# ADC.net
KiCad netlist of a schematic drawn in Altium Designer
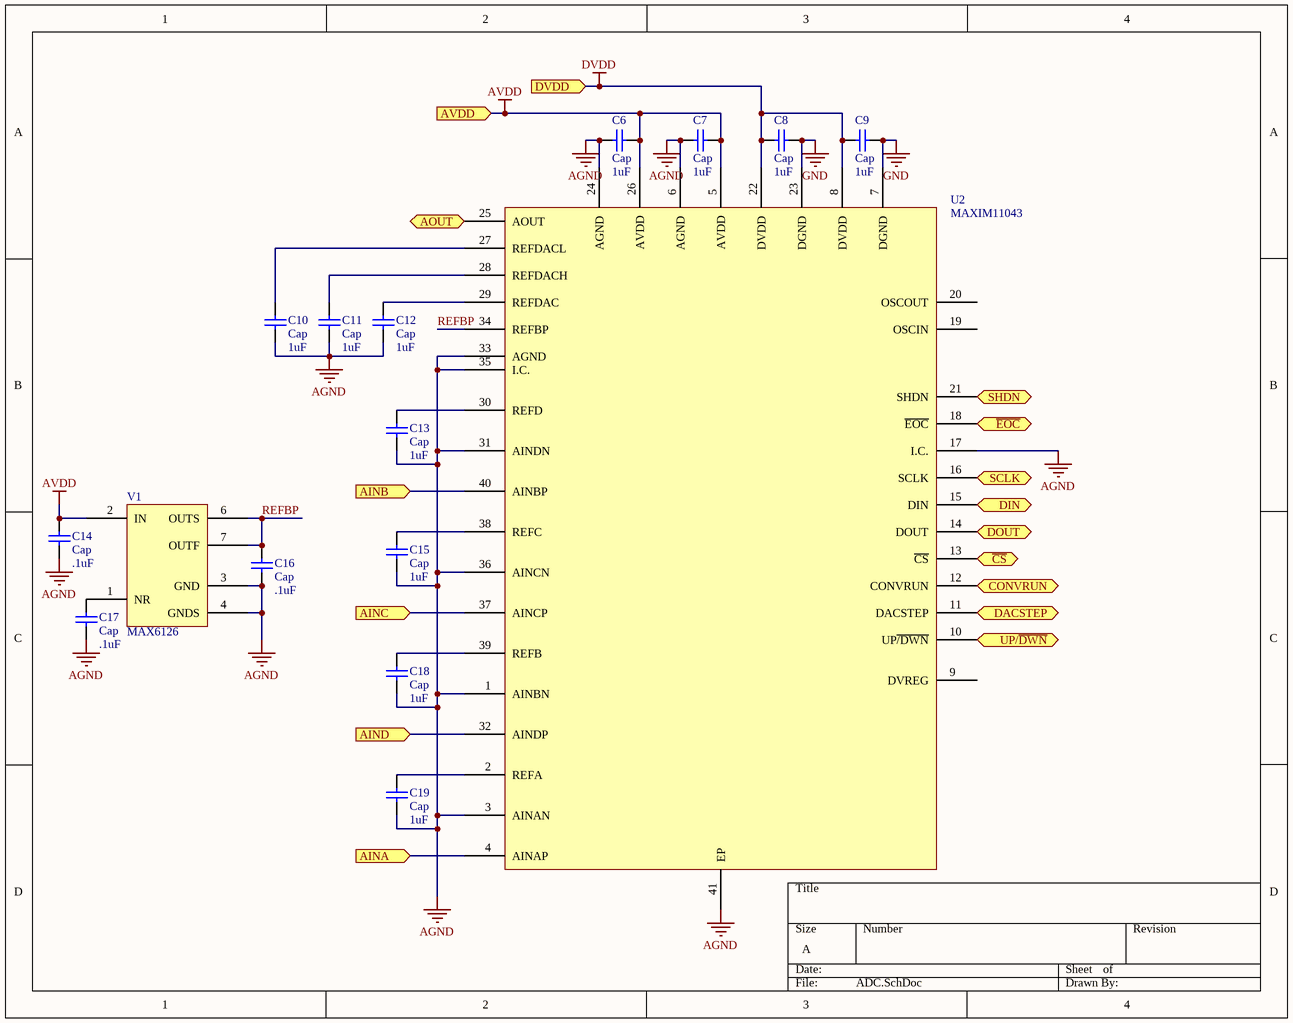
[diagram p0: ADC.SchDoc]

(export (version "E")
  (design (tool "Eeschema 10.0.6"))
  (components
    (comp (ref "C6")
      (value "Cap")
      (footprint "1608[0603]")
      (description "Capacitor")
      (fields (field (name "ALTIUM_VALUE") "1uF") (field (name "PUBLISHER") "Altium Limited"))
      (libsource (lib "Miscellaneous Devices") (part "Cap"))
    )
    (comp (ref "C7")
      (value "Cap")
      (footprint "1608[0603]")
      (description "Capacitor")
      (fields (field (name "ALTIUM_VALUE") "1uF") (field (name "PUBLISHER") "Altium Limited"))
      (libsource (lib "Miscellaneous Devices") (part "Cap"))
    )
    (comp (ref "C8")
      (value "Cap")
      (footprint "1608[0603]")
      (description "Capacitor")
      (fields (field (name "ALTIUM_VALUE") "1uF") (field (name "PUBLISHER") "Altium Limited"))
      (libsource (lib "Miscellaneous Devices") (part "Cap"))
    )
    (comp (ref "C9")
      (value "Cap")
      (footprint "1608[0603]")
      (description "Capacitor")
      (fields (field (name "ALTIUM_VALUE") "1uF") (field (name "PUBLISHER") "Altium Limited"))
      (libsource (lib "Miscellaneous Devices") (part "Cap"))
    )
    (comp (ref "C10")
      (value "Cap")
      (footprint "1608[0603]")
      (description "Capacitor")
      (fields (field (name "ALTIUM_VALUE") "1uF") (field (name "PUBLISHER") "Altium Limited"))
      (libsource (lib "Miscellaneous Devices") (part "Cap"))
    )
    (comp (ref "C11")
      (value "Cap")
      (footprint "1608[0603]")
      (description "Capacitor")
      (fields (field (name "ALTIUM_VALUE") "1uF") (field (name "PUBLISHER") "Altium Limited"))
      (libsource (lib "Miscellaneous Devices") (part "Cap"))
    )
    (comp (ref "C12")
      (value "Cap")
      (footprint "1608[0603]")
      (description "Capacitor")
      (fields (field (name "ALTIUM_VALUE") "1uF") (field (name "PUBLISHER") "Altium Limited"))
      (libsource (lib "Miscellaneous Devices") (part "Cap"))
    )
    (comp (ref "C13")
      (value "Cap")
      (footprint "1608[0603]")
      (description "Capacitor")
      (fields (field (name "ALTIUM_VALUE") "1uF") (field (name "PUBLISHER") "Altium Limited"))
      (libsource (lib "Miscellaneous Devices") (part "Cap"))
    )
    (comp (ref "C14")
      (value "Cap")
      (footprint "1608[0603]")
      (description "Capacitor")
      (fields (field (name "ALTIUM_VALUE") ".1uF") (field (name "PUBLISHER") "Altium Limited"))
      (libsource (lib "Miscellaneous Devices") (part "Cap"))
    )
    (comp (ref "C15")
      (value "Cap")
      (footprint "1608[0603]")
      (description "Capacitor")
      (fields (field (name "ALTIUM_VALUE") "1uF") (field (name "PUBLISHER") "Altium Limited"))
      (libsource (lib "Miscellaneous Devices") (part "Cap"))
    )
    (comp (ref "C16")
      (value "Cap")
      (footprint "1608[0603]")
      (description "Capacitor")
      (fields (field (name "ALTIUM_VALUE") ".1uF") (field (name "PUBLISHER") "Altium Limited"))
      (libsource (lib "Miscellaneous Devices") (part "Cap"))
    )
    (comp (ref "C17")
      (value "Cap")
      (footprint "1608[0603]")
      (description "Capacitor")
      (fields (field (name "ALTIUM_VALUE") ".1uF") (field (name "PUBLISHER") "Altium Limited"))
      (libsource (lib "Miscellaneous Devices") (part "Cap"))
    )
    (comp (ref "C18")
      (value "Cap")
      (footprint "1608[0603]")
      (description "Capacitor")
      (fields (field (name "ALTIUM_VALUE") "1uF") (field (name "PUBLISHER") "Altium Limited"))
      (libsource (lib "Miscellaneous Devices") (part "Cap"))
    )
    (comp (ref "C19")
      (value "Cap")
      (footprint "1608[0603]")
      (description "Capacitor")
      (fields (field (name "ALTIUM_VALUE") "1uF") (field (name "PUBLISHER") "Altium Limited"))
      (libsource (lib "Miscellaneous Devices") (part "Cap"))
    )
    (comp (ref "U2")
      (value "MAXIM11043")
      (footprint "21-0141I_T406600")
      (libsource (lib "MAXIM11043") (part "MAXIM11043"))
    )
    (comp (ref "V1")
      (value "MAX6126")
      (footprint "SOIC127P600X175-8N(lm358)")
      (libsource (lib "MAX6126") (part "MAX6126"))
    )
  )
  (nets
    (net (code "1") (name "/AINA") (class "Default")
      (node (ref "U2") (pin "4") (pinfunction "AINAP_4") (pintype "passive"))
    )
    (net (code "2") (name "/AINB") (class "Default")
      (node (ref "U2") (pin "40") (pinfunction "AINBP_40") (pintype "passive"))
    )
    (net (code "3") (name "/AINC") (class "Default")
      (node (ref "U2") (pin "37") (pinfunction "AINCP_37") (pintype "passive"))
    )
    (net (code "4") (name "/AIND") (class "Default")
      (node (ref "U2") (pin "32") (pinfunction "AINDP_32") (pintype "passive"))
    )
    (net (code "5") (name "/AOUT") (class "Default")
      (node (ref "U2") (pin "25") (pinfunction "AOUT_25") (pintype "passive"))
    )
    (net (code "6") (name "/CONVRUN") (class "Default")
      (node (ref "U2") (pin "12") (pinfunction "CONVRUN_12") (pintype "passive"))
    )
    (net (code "7") (name "/DACSTEP") (class "Default")
      (node (ref "U2") (pin "11") (pinfunction "DACSTEP_11") (pintype "passive"))
    )
    (net (code "8") (name "/DIN") (class "Default")
      (node (ref "U2") (pin "15") (pinfunction "DIN_15") (pintype "passive"))
    )
    (net (code "9") (name "/DOUT") (class "Default")
      (node (ref "U2") (pin "14") (pinfunction "DOUT_14") (pintype "passive"))
    )
    (net (code "10") (name "/REFBP") (class "Default")
      (node (ref "C16") (pin "2") (pinfunction "2_2") (pintype "passive"))
      (node (ref "U2") (pin "34") (pinfunction "REFBP_34") (pintype "passive"))
      (node (ref "V1") (pin "6") (pinfunction "OUTS_6") (pintype "passive"))
      (node (ref "V1") (pin "7") (pinfunction "OUTF_7") (pintype "passive"))
    )
    (net (code "11") (name "/SCLK") (class "Default")
      (node (ref "U2") (pin "16") (pinfunction "SCLK_16") (pintype "passive"))
    )
    (net (code "12") (name "/SHDN") (class "Default")
      (node (ref "U2") (pin "21") (pinfunction "SHDN_21") (pintype "passive"))
    )
    (net (code "13") (name "/UP{slash}~{DWN}") (class "Default")
      (node (ref "U2") (pin "10") (pinfunction "UP~{/DWN}_10") (pintype "passive"))
    )
    (net (code "14") (name "/~{CS}") (class "Default")
      (node (ref "U2") (pin "13") (pinfunction "~{CS}_13") (pintype "passive"))
    )
    (net (code "15") (name "/~{EOC}") (class "Default")
      (node (ref "U2") (pin "18") (pinfunction "~{EOC}_18") (pintype "passive"))
    )
    (net (code "16") (name "AGND") (class "Default")
      (node (ref "C10") (pin "1") (pinfunction "1_1") (pintype "passive"))
      (node (ref "C11") (pin "1") (pinfunction "1_1") (pintype "passive"))
      (node (ref "C12") (pin "1") (pinfunction "1_1") (pintype "passive"))
      (node (ref "C13") (pin "1") (pinfunction "1_1") (pintype "passive"))
      (node (ref "C14") (pin "1") (pinfunction "1_1") (pintype "passive"))
      (node (ref "C15") (pin "1") (pinfunction "1_1") (pintype "passive"))
      (node (ref "C16") (pin "1") (pinfunction "1_1") (pintype "passive"))
      (node (ref "C17") (pin "1") (pinfunction "1_1") (pintype "passive"))
      (node (ref "C18") (pin "1") (pinfunction "1_1") (pintype "passive"))
      (node (ref "C19") (pin "1") (pinfunction "1_1") (pintype "passive"))
      (node (ref "C6") (pin "1") (pinfunction "1_1") (pintype "passive"))
      (node (ref "C7") (pin "1") (pinfunction "1_1") (pintype "passive"))
      (node (ref "U2") (pin "1") (pinfunction "AINBN_1") (pintype "passive"))
      (node (ref "U2") (pin "17") (pinfunction "I.C._17") (pintype "passive"))
      (node (ref "U2") (pin "24") (pinfunction "AGND_24") (pintype "passive"))
      (node (ref "U2") (pin "3") (pinfunction "AINAN_3") (pintype "passive"))
      (node (ref "U2") (pin "31") (pinfunction "AINDN_31") (pintype "passive"))
      (node (ref "U2") (pin "33") (pinfunction "AGND_33") (pintype "passive"))
      (node (ref "U2") (pin "35") (pinfunction "I.C._35") (pintype "passive"))
      (node (ref "U2") (pin "36") (pinfunction "AINCN_36") (pintype "passive"))
      (node (ref "U2") (pin "41") (pinfunction "EP_41") (pintype "passive"))
      (node (ref "U2") (pin "6") (pinfunction "AGND_6") (pintype "passive"))
      (node (ref "V1") (pin "3") (pinfunction "GND_3") (pintype "passive"))
      (node (ref "V1") (pin "4") (pinfunction "GNDS_4") (pintype "passive"))
    )
    (net (code "17") (name "AVDD") (class "Default")
      (node (ref "C14") (pin "2") (pinfunction "2_2") (pintype "passive"))
      (node (ref "C6") (pin "2") (pinfunction "2_2") (pintype "passive"))
      (node (ref "C7") (pin "2") (pinfunction "2_2") (pintype "passive"))
      (node (ref "U2") (pin "26") (pinfunction "AVDD_26") (pintype "passive"))
      (node (ref "U2") (pin "5") (pinfunction "AVDD_5") (pintype "passive"))
      (node (ref "V1") (pin "2") (pinfunction "IN_2") (pintype "passive"))
    )
    (net (code "18") (name "DVDD") (class "Default")
      (node (ref "C8") (pin "1") (pinfunction "1_1") (pintype "passive"))
      (node (ref "C9") (pin "1") (pinfunction "1_1") (pintype "passive"))
      (node (ref "U2") (pin "22") (pinfunction "DVDD_22") (pintype "passive"))
      (node (ref "U2") (pin "8") (pinfunction "DVDD_8") (pintype "passive"))
    )
    (net (code "19") (name "GND") (class "Default")
      (node (ref "C8") (pin "2") (pinfunction "2_2") (pintype "passive"))
      (node (ref "C9") (pin "2") (pinfunction "2_2") (pintype "passive"))
      (node (ref "U2") (pin "23") (pinfunction "DGND_23") (pintype "passive"))
      (node (ref "U2") (pin "7") (pinfunction "DGND_7") (pintype "passive"))
    )
    (net (code "20") (name "Net-(U2-REFA)") (class "Default")
      (node (ref "C19") (pin "2") (pinfunction "2_2") (pintype "passive"))
      (node (ref "U2") (pin "2") (pinfunction "REFA_2") (pintype "passive"))
    )
    (net (code "21") (name "Net-(U2-REFB)") (class "Default")
      (node (ref "C18") (pin "2") (pinfunction "2_2") (pintype "passive"))
      (node (ref "U2") (pin "39") (pinfunction "REFB_39") (pintype "passive"))
    )
    (net (code "22") (name "Net-(U2-REFC)") (class "Default")
      (node (ref "C15") (pin "2") (pinfunction "2_2") (pintype "passive"))
      (node (ref "U2") (pin "38") (pinfunction "REFC_38") (pintype "passive"))
    )
    (net (code "23") (name "Net-(U2-REFD)") (class "Default")
      (node (ref "C13") (pin "2") (pinfunction "2_2") (pintype "passive"))
      (node (ref "U2") (pin "30") (pinfunction "REFD_30") (pintype "passive"))
    )
    (net (code "24") (name "Net-(U2-REFDAC)") (class "Default")
      (node (ref "C12") (pin "2") (pinfunction "2_2") (pintype "passive"))
      (node (ref "U2") (pin "29") (pinfunction "REFDAC_29") (pintype "passive"))
    )
    (net (code "25") (name "Net-(U2-REFDACH)") (class "Default")
      (node (ref "C11") (pin "2") (pinfunction "2_2") (pintype "passive"))
      (node (ref "U2") (pin "28") (pinfunction "REFDACH_28") (pintype "passive"))
    )
    (net (code "26") (name "Net-(U2-REFDACL)") (class "Default")
      (node (ref "C10") (pin "2") (pinfunction "2_2") (pintype "passive"))
      (node (ref "U2") (pin "27") (pinfunction "REFDACL_27") (pintype "passive"))
    )
    (net (code "27") (name "Net-(V1-NR)") (class "Default")
      (node (ref "C17") (pin "2") (pinfunction "2_2") (pintype "passive"))
      (node (ref "V1") (pin "1") (pinfunction "NR_1") (pintype "passive"))
    )
    (net (code "28") (name "unconnected-(U2-DVREG-Pad9)") (class "Default")
      (node (ref "U2") (pin "9") (pinfunction "DVREG_9") (pintype "passive"))
    )
    (net (code "29") (name "unconnected-(U2-OSCIN-Pad19)") (class "Default")
      (node (ref "U2") (pin "19") (pinfunction "OSCIN_19") (pintype "passive"))
    )
    (net (code "30") (name "unconnected-(U2-OSCOUT-Pad20)") (class "Default")
      (node (ref "U2") (pin "20") (pinfunction "OSCOUT_20") (pintype "passive"))
    )
  )
)
